# TiltyOmni.net
KiCad netlist of a schematic drawn in EAGLE
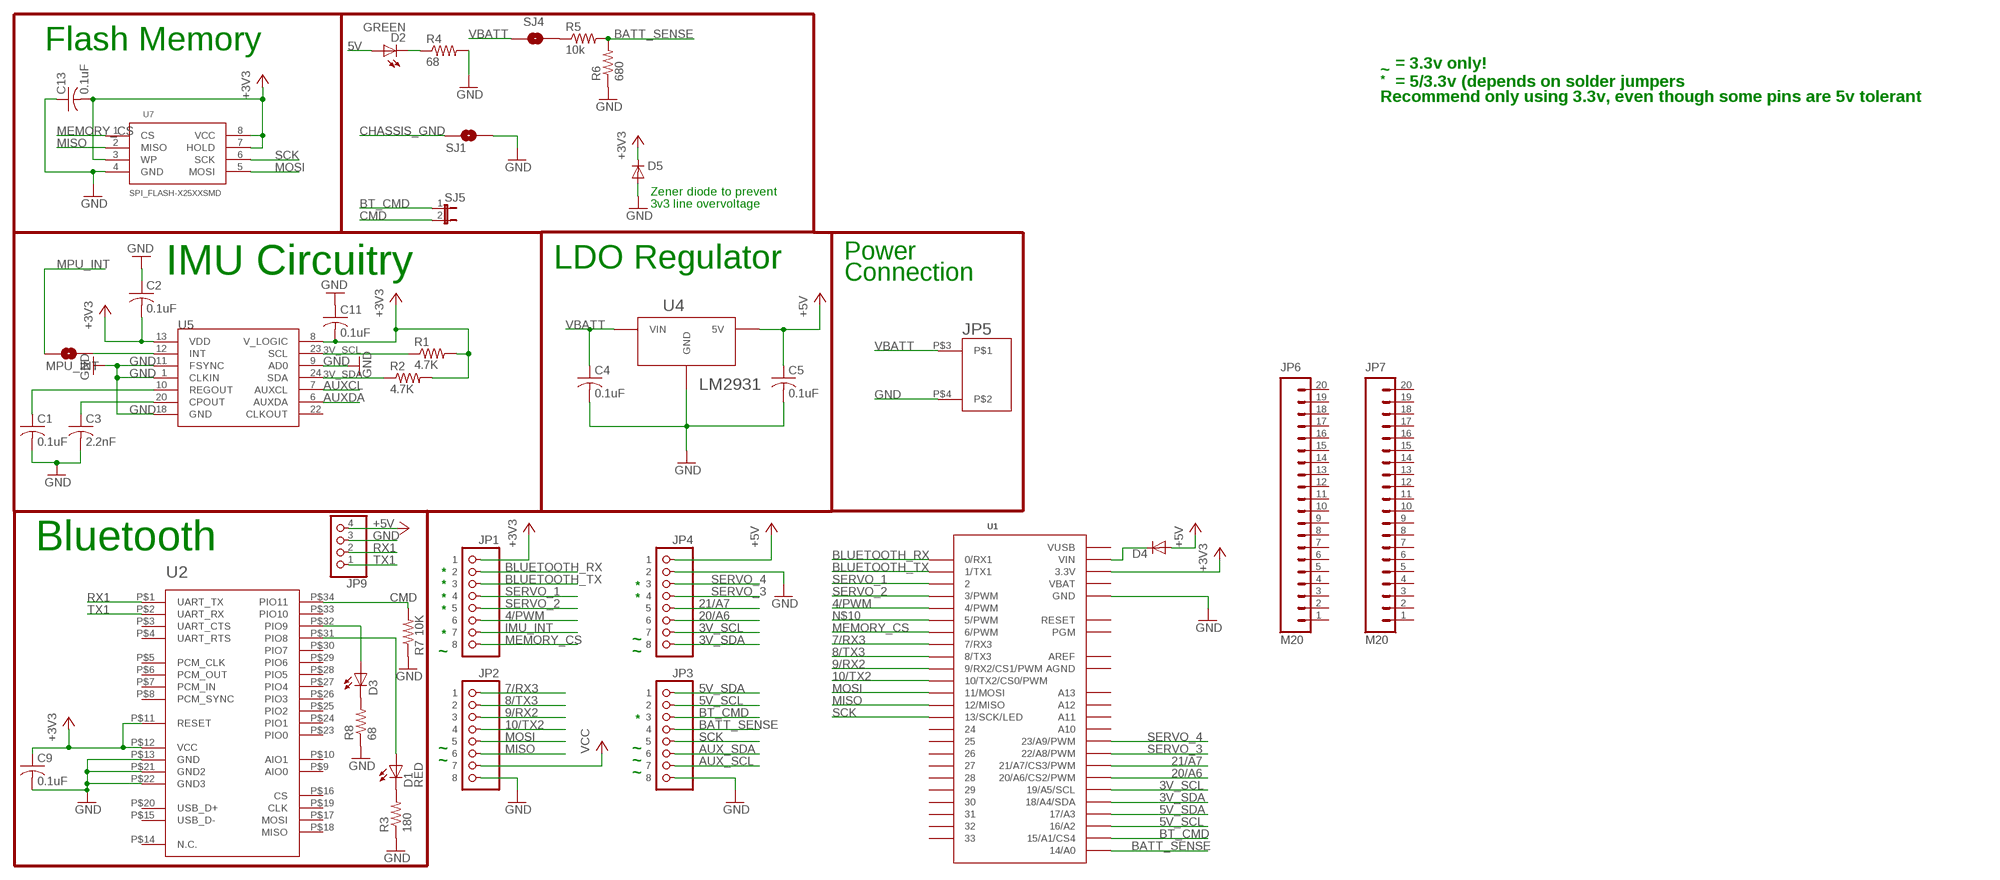
[diagram p0: schematic, sheet 1]

(export (version "E")
  (design (tool "Eeschema 10.0.6"))
  (components
    (comp (ref "C1")
      (value "0.1uF")
      (footprint "eagle-import:C0603")
      (libsource (lib "eagle-import") (part "C-USC0603"))
    )
    (comp (ref "C2")
      (value "0.1uF")
      (footprint "eagle-import:C0603")
      (libsource (lib "eagle-import") (part "C-USC0603"))
    )
    (comp (ref "C3")
      (value "2.2nF")
      (footprint "eagle-import:C0603")
      (libsource (lib "eagle-import") (part "C-USC0603"))
    )
    (comp (ref "C4")
      (value "0.1uF")
      (footprint "eagle-import:C0603")
      (libsource (lib "eagle-import") (part "C-USC0603"))
    )
    (comp (ref "C5")
      (value "0.1uF")
      (footprint "eagle-import:C0603")
      (libsource (lib "eagle-import") (part "C-USC0603"))
    )
    (comp (ref "C9")
      (value "0.1uF")
      (footprint "eagle-import:C0603")
      (libsource (lib "eagle-import") (part "C-USC0603"))
    )
    (comp (ref "C11")
      (value "0.1uF")
      (footprint "eagle-import:C0603")
      (libsource (lib "eagle-import") (part "C-USC0603"))
    )
    (comp (ref "C13")
      (value "0.1uF")
      (footprint "eagle-import:C0603")
      (libsource (lib "eagle-import") (part "C-USC0603"))
    )
    (comp (ref "D1")
      (value "RED")
      (footprint "eagle-import:LED-0805")
      (libsource (lib "eagle-import") (part "LED-GREENLED-0805_NO_SILK"))
    )
    (comp (ref "D2")
      (value "GREEN")
      (footprint "eagle-import:LED-0805")
      (libsource (lib "eagle-import") (part "LED-GREENLED-0805_NO_SILK"))
    )
    (comp (ref "D3")
      (value "YELLOW")
      (footprint "eagle-import:LED-0805")
      (libsource (lib "eagle-import") (part "LED-GREENLED-0805_NO_SILK"))
    )
    (comp (ref "D4")
      (value "DIODESOT23")
      (footprint "eagle-import:SOT23-3")
      (libsource (lib "eagle-import") (part "DIODESOT23"))
    )
    (comp (ref "D5")
      (value "DIODESOT23")
      (footprint "eagle-import:SOT23-3")
      (fields (field (name "PART#") "BZX84C3V3LT1GOSCT-ND"))
      (libsource (lib "eagle-import") (part "DIODESOT23"))
    )
    (comp (ref "JP1")
      (value "8-PIN_HEADER")
      (footprint "eagle-import:8-PIN_RECEPTACLE_LOCK_NO-SS")
      (libsource (lib "eagle-import") (part "8-PIN_HEADER"))
    )
    (comp (ref "JP2")
      (value "8-PIN_HEADER")
      (footprint "eagle-import:8-PIN_RECEPTACLE_LOCK_NO-SS")
      (libsource (lib "eagle-import") (part "8-PIN_HEADER"))
    )
    (comp (ref "JP3")
      (value "8-PIN_HEADER")
      (footprint "eagle-import:8-PIN_RECEPTACLE_LOCK_NO-SS")
      (libsource (lib "eagle-import") (part "8-PIN_HEADER"))
    )
    (comp (ref "JP4")
      (value "8-PIN_HEADER")
      (footprint "eagle-import:8-PIN_RECEPTACLE_LOCK_NO-SS")
      (libsource (lib "eagle-import") (part "8-PIN_HEADER"))
    )
    (comp (ref "JP5")
      (value "2-POS_SMD_TERM_BLOCK")
      (footprint "eagle-import:2-POS_SMD_TERMINAL_BLOCK")
      (fields (field (name "PART#") "277-2337-1-ND"))
      (libsource (lib "eagle-import") (part "2-POS_SMD_TERM_BLOCK"))
    )
    (comp (ref "JP6")
      (value "M20")
      (footprint "eagle-import:1X20")
      (libsource (lib "eagle-import") (part "M20"))
    )
    (comp (ref "JP7")
      (value "M20")
      (footprint "eagle-import:1X20")
      (libsource (lib "eagle-import") (part "M20"))
    )
    (comp (ref "JP9")
      (value "PINHD-1X41X04_NO_SS_LOCKING")
      (footprint "eagle-import:1X04_NO_SS_LOCKING")
      (libsource (lib "eagle-import") (part "PINHD-1X41X04_NO_SS_LOCKING"))
    )
    (comp (ref "MPU_INT")
      (value "SOLDERJUMPERNO")
      (footprint "eagle-import:SJ_2S-NO")
      (libsource (lib "eagle-import") (part "SOLDERJUMPERNO"))
    )
    (comp (ref "R1")
      (value "4.7K")
      (footprint "eagle-import:R0603")
      (libsource (lib "eagle-import") (part "R-US_R0603"))
    )
    (comp (ref "R2")
      (value "4.7K")
      (footprint "eagle-import:R0603")
      (libsource (lib "eagle-import") (part "R-US_R0603"))
    )
    (comp (ref "R3")
      (value "180")
      (footprint "eagle-import:R0603")
      (libsource (lib "eagle-import") (part "R-US_R0603"))
    )
    (comp (ref "R4")
      (value "68")
      (footprint "eagle-import:R0603")
      (libsource (lib "eagle-import") (part "R-US_R0603"))
    )
    (comp (ref "R5")
      (value "10k")
      (footprint "eagle-import:R0603")
      (libsource (lib "eagle-import") (part "R-US_R0603"))
    )
    (comp (ref "R6")
      (value "680")
      (footprint "eagle-import:R0603")
      (libsource (lib "eagle-import") (part "R-US_R0603"))
    )
    (comp (ref "R7")
      (value "10K")
      (footprint "eagle-import:R0603")
      (libsource (lib "eagle-import") (part "R-US_R0603"))
    )
    (comp (ref "R8")
      (value "68")
      (footprint "eagle-import:R0603")
      (libsource (lib "eagle-import") (part "R-US_R0603"))
    )
    (comp (ref "SJ1")
      (value "SOLDERJUMPERNO")
      (footprint "eagle-import:SJ_2S-NO")
      (libsource (lib "eagle-import") (part "SOLDERJUMPERNO"))
    )
    (comp (ref "SJ4")
      (value "SOLDERJUMPERTRACE")
      (footprint "eagle-import:SJ_2S-TRACE")
      (libsource (lib "eagle-import") (part "SOLDERJUMPERTRACE"))
    )
    (comp (ref "SJ5")
      (value "JUMPER-2SMD-NC")
      (footprint "eagle-import:SJ_2S")
      (libsource (lib "eagle-import") (part "JUMPER-2SMD-NC"))
    )
    (comp (ref "U1")
      (value "TEENSY_3.0_ALLPINS")
      (footprint "eagle-import:TEENSY_3.0_ALLPINS")
      (libsource (lib "eagle-import") (part "TEENSY_3.0_ALLPINS"))
    )
    (comp (ref "U2")
      (value "HC-09_BREAKOUT")
      (footprint "eagle-import:HC-09_BREAKOUT")
      (libsource (lib "eagle-import") (part "HC-09_BREAKOUT"))
    )
    (comp (ref "U4")
      (value "LM2931")
      (footprint "eagle-import:TO263")
      (libsource (lib "eagle-import") (part "LM2931"))
    )
    (comp (ref "U5")
      (value "MPU-6050")
      (footprint "eagle-import:QFN-24")
      (libsource (lib "eagle-import") (part "MPU-6050"))
    )
    (comp (ref "U7")
      (value "SPI_FLASH-X25XXSMD")
      (footprint "eagle-import:SO08")
      (fields (field (name "PART#") "S25FL204K0TMFI043"))
      (libsource (lib "eagle-import") (part "SPI_FLASH-X25XXSMD"))
    )
  )
  (nets
    (net (code "1") (name "+3V3") (class "Default")
      (node (ref "C11") (pin "2") (pinfunction "2_2") (pintype "passive"))
      (node (ref "C13") (pin "2") (pinfunction "2_2") (pintype "passive"))
      (node (ref "C2") (pin "2") (pinfunction "2_2") (pintype "passive"))
      (node (ref "C9") (pin "1") (pinfunction "1_1") (pintype "passive"))
      (node (ref "D5") (pin "3") (pinfunction "C_3") (pintype "passive"))
      (node (ref "JP1") (pin "P$1") (pinfunction "1_P$1") (pintype "passive"))
      (node (ref "R1") (pin "2") (pinfunction "2_2") (pintype "passive"))
      (node (ref "R2") (pin "2") (pinfunction "2_2") (pintype "passive"))
      (node (ref "U1") (pin "3.3V") (pinfunction "3.3V_3.3V") (pintype "power_in"))
      (node (ref "U1") (pin "3.3V1") (pinfunction "3.3V_3.3V1") (pintype "power_in"))
      (node (ref "U1") (pin "3.3V2") (pinfunction "3.3V_3.3V2") (pintype "power_in"))
      (node (ref "U2") (pin "P$11") (pinfunction "RESET_P$11") (pintype "bidirectional"))
      (node (ref "U2") (pin "P$12") (pinfunction "VCC_P$12") (pintype "bidirectional"))
      (node (ref "U5") (pin "13") (pinfunction "VDD_13") (pintype "bidirectional"))
      (node (ref "U5") (pin "8") (pinfunction "V_LOGIC_8") (pintype "bidirectional"))
      (node (ref "U7") (pin "3") (pinfunction "WP_3") (pintype "bidirectional"))
      (node (ref "U7") (pin "7") (pinfunction "HOLD_7") (pintype "bidirectional"))
      (node (ref "U7") (pin "8") (pinfunction "VCC_8") (pintype "bidirectional"))
    )
    (net (code "2") (name "+5V") (class "Default")
      (node (ref "C5") (pin "1") (pinfunction "1_1") (pintype "passive"))
      (node (ref "D4") (pin "1") (pinfunction "A_1") (pintype "passive"))
      (node (ref "JP4") (pin "P$1") (pinfunction "1_P$1") (pintype "passive"))
      (node (ref "JP9") (pin "4") (pinfunction "4_4") (pintype "passive"))
      (node (ref "U4") (pin "P$3") (pinfunction "5V_P$3") (pintype "bidirectional"))
    )
    (net (code "3") (name "/3V_SCL") (class "Default")
      (node (ref "JP4") (pin "P$7") (pinfunction "7_P$7") (pintype "passive"))
      (node (ref "R1") (pin "1") (pinfunction "1_1") (pintype "passive"))
      (node (ref "U1") (pin "19/A5") (pinfunction "19/A5/SCL_19/A5") (pintype "bidirectional"))
      (node (ref "U5") (pin "23") (pinfunction "SCL_23") (pintype "bidirectional"))
    )
    (net (code "4") (name "/3V_SDA") (class "Default")
      (node (ref "JP4") (pin "P$8") (pinfunction "8_P$8") (pintype "passive"))
      (node (ref "R2") (pin "1") (pinfunction "1_1") (pintype "passive"))
      (node (ref "U1") (pin "18/A4") (pinfunction "18/A4/SDA_18/A4") (pintype "bidirectional"))
      (node (ref "U5") (pin "24") (pinfunction "SDA_24") (pintype "bidirectional"))
    )
    (net (code "5") (name "/4{slash}PWM") (class "Default")
      (node (ref "JP1") (pin "P$6") (pinfunction "6_P$6") (pintype "passive"))
      (node (ref "U1") (pin "4") (pinfunction "4/PWM_4") (pintype "bidirectional"))
    )
    (net (code "6") (name "/5V") (class "Default")
      (node (ref "D2") (pin "1") (pinfunction "A_1") (pintype "passive"))
    )
    (net (code "7") (name "/5V_SCL") (class "Default")
      (node (ref "JP3") (pin "P$2") (pinfunction "2_P$2") (pintype "passive"))
      (node (ref "U1") (pin "16/A2") (pinfunction "16/A2_16/A2") (pintype "bidirectional"))
    )
    (net (code "8") (name "/5V_SDA") (class "Default")
      (node (ref "JP3") (pin "P$1") (pinfunction "1_P$1") (pintype "passive"))
      (node (ref "U1") (pin "17/A3") (pinfunction "17/A3_17/A3") (pintype "bidirectional"))
    )
    (net (code "9") (name "/7{slash}RX3") (class "Default")
      (node (ref "JP2") (pin "P$1") (pinfunction "1_P$1") (pintype "passive"))
      (node (ref "U1") (pin "7") (pinfunction "7/RX3_7") (pintype "bidirectional"))
    )
    (net (code "10") (name "/8{slash}TX3") (class "Default")
      (node (ref "JP2") (pin "P$2") (pinfunction "2_P$2") (pintype "passive"))
      (node (ref "U1") (pin "8") (pinfunction "8/TX3_8") (pintype "bidirectional"))
    )
    (net (code "11") (name "/9{slash}RX2") (class "Default")
      (node (ref "JP2") (pin "P$3") (pinfunction "3_P$3") (pintype "passive"))
      (node (ref "U1") (pin "9") (pinfunction "9/RX2/CS1/PWM_9") (pintype "bidirectional"))
    )
    (net (code "12") (name "/10{slash}TX2") (class "Default")
      (node (ref "JP2") (pin "P$4") (pinfunction "4_P$4") (pintype "passive"))
      (node (ref "U1") (pin "10") (pinfunction "10/TX2/CS0/PWM_10") (pintype "bidirectional"))
    )
    (net (code "13") (name "/20{slash}A6") (class "Default")
      (node (ref "JP4") (pin "P$6") (pinfunction "6_P$6") (pintype "passive"))
      (node (ref "U1") (pin "20/A6") (pinfunction "20/A6/CS2/PWM_20/A6") (pintype "bidirectional"))
    )
    (net (code "14") (name "/21{slash}A7") (class "Default")
      (node (ref "JP4") (pin "P$5") (pinfunction "5_P$5") (pintype "passive"))
      (node (ref "U1") (pin "21/A7") (pinfunction "21/A7/CS3/PWM_21/A7") (pintype "bidirectional"))
    )
    (net (code "15") (name "/AGND") (class "Default")
      (node (ref "U1") (pin "AGND") (pinfunction "AGND_AGND") (pintype "power_in"))
    )
    (net (code "16") (name "/AREF") (class "Default")
      (node (ref "U1") (pin "AREF") (pinfunction "AREF_AREF") (pintype "power_in"))
    )
    (net (code "17") (name "/AUXCL") (class "Default")
      (node (ref "U5") (pin "7") (pinfunction "AUXCL_7") (pintype "bidirectional"))
    )
    (net (code "18") (name "/AUXDA") (class "Default")
      (node (ref "U5") (pin "6") (pinfunction "AUXDA_6") (pintype "bidirectional"))
    )
    (net (code "19") (name "/AUX_SCL") (class "Default")
      (node (ref "JP3") (pin "P$7") (pinfunction "7_P$7") (pintype "passive"))
    )
    (net (code "20") (name "/AUX_SDA") (class "Default")
      (node (ref "JP3") (pin "P$6") (pinfunction "6_P$6") (pintype "passive"))
    )
    (net (code "21") (name "/BATT_SENSE") (class "Default")
      (node (ref "JP3") (pin "P$4") (pinfunction "4_P$4") (pintype "passive"))
      (node (ref "R5") (pin "2") (pinfunction "2_2") (pintype "passive"))
      (node (ref "R6") (pin "2") (pinfunction "2_2") (pintype "passive"))
      (node (ref "U1") (pin "14/A0") (pinfunction "14/A0_14/A0") (pintype "bidirectional"))
    )
    (net (code "22") (name "/BLUETOOTH_RX") (class "Default")
      (node (ref "JP1") (pin "P$2") (pinfunction "2_P$2") (pintype "passive"))
      (node (ref "U1") (pin "0") (pinfunction "0/RX1_0") (pintype "bidirectional"))
    )
    (net (code "23") (name "/BLUETOOTH_TX") (class "Default")
      (node (ref "JP1") (pin "P$3") (pinfunction "3_P$3") (pintype "passive"))
      (node (ref "U1") (pin "1") (pinfunction "1/TX1_1") (pintype "bidirectional"))
    )
    (net (code "24") (name "/BT_CMD") (class "Default")
      (node (ref "JP3") (pin "P$3") (pinfunction "3_P$3") (pintype "passive"))
      (node (ref "SJ5") (pin "1") (pinfunction "1_1") (pintype "passive"))
      (node (ref "U1") (pin "15/A1") (pinfunction "15/A1/CS4_15/A1") (pintype "bidirectional"))
    )
    (net (code "25") (name "/CHASSIS_GND") (class "Default")
      (node (ref "SJ1") (pin "1") (pinfunction "1_1") (pintype "passive"))
    )
    (net (code "26") (name "/CMD") (class "Default")
      (node (ref "R7") (pin "2") (pinfunction "2_2") (pintype "passive"))
      (node (ref "SJ5") (pin "2") (pinfunction "2_2") (pintype "passive"))
      (node (ref "U2") (pin "P$34") (pinfunction "PIO11_P$34") (pintype "bidirectional"))
    )
    (net (code "27") (name "/IMU_INT") (class "Default")
      (node (ref "JP1") (pin "P$7") (pinfunction "7_P$7") (pintype "passive"))
    )
    (net (code "28") (name "/MEMORY_CS") (class "Default")
      (node (ref "JP1") (pin "P$8") (pinfunction "8_P$8") (pintype "passive"))
      (node (ref "U1") (pin "6") (pinfunction "6/PWM_6") (pintype "bidirectional"))
      (node (ref "U7") (pin "1") (pinfunction "CS_1") (pintype "bidirectional"))
    )
    (net (code "29") (name "/MISO") (class "Default")
      (node (ref "JP2") (pin "P$6") (pinfunction "6_P$6") (pintype "passive"))
      (node (ref "U1") (pin "12") (pinfunction "12/MISO_12") (pintype "bidirectional"))
      (node (ref "U7") (pin "2") (pinfunction "MISO_2") (pintype "bidirectional"))
    )
    (net (code "30") (name "/MOSI") (class "Default")
      (node (ref "JP2") (pin "P$5") (pinfunction "5_P$5") (pintype "passive"))
      (node (ref "U1") (pin "11") (pinfunction "11/MOSI_11") (pintype "bidirectional"))
      (node (ref "U7") (pin "5") (pinfunction "MOSI_5") (pintype "bidirectional"))
    )
    (net (code "31") (name "/MPU_INT") (class "Default")
      (node (ref "MPU_INT") (pin "1") (pinfunction "1_1") (pintype "passive"))
    )
    (net (code "32") (name "/N$10") (class "Default")
      (node (ref "U1") (pin "5") (pinfunction "5/PWM_5") (pintype "bidirectional"))
    )
    (net (code "33") (name "/RX1") (class "Default")
      (node (ref "JP9") (pin "2") (pinfunction "2_2") (pintype "passive"))
      (node (ref "U2") (pin "P$1") (pinfunction "UART_TX_P$1") (pintype "bidirectional"))
    )
    (net (code "34") (name "/SCK") (class "Default")
      (node (ref "JP3") (pin "P$5") (pinfunction "5_P$5") (pintype "passive"))
      (node (ref "U1") (pin "13") (pinfunction "13/SCK/LED_13") (pintype "bidirectional"))
      (node (ref "U7") (pin "6") (pinfunction "SCK_6") (pintype "bidirectional"))
    )
    (net (code "35") (name "/SERVO_1") (class "Default")
      (node (ref "JP1") (pin "P$4") (pinfunction "4_P$4") (pintype "passive"))
      (node (ref "U1") (pin "2") (pinfunction "2_2") (pintype "bidirectional"))
    )
    (net (code "36") (name "/SERVO_2") (class "Default")
      (node (ref "JP1") (pin "P$5") (pinfunction "5_P$5") (pintype "passive"))
      (node (ref "U1") (pin "3") (pinfunction "3/PWM_3") (pintype "bidirectional"))
    )
    (net (code "37") (name "/SERVO_3") (class "Default")
      (node (ref "JP4") (pin "P$4") (pinfunction "4_P$4") (pintype "passive"))
      (node (ref "U1") (pin "22/A8") (pinfunction "22/A8/PWM_22/A8") (pintype "bidirectional"))
    )
    (net (code "38") (name "/SERVO_4") (class "Default")
      (node (ref "JP4") (pin "P$3") (pinfunction "3_P$3") (pintype "passive"))
      (node (ref "U1") (pin "23/A9") (pinfunction "23/A9/PWM_23/A9") (pintype "bidirectional"))
    )
    (net (code "39") (name "/TX1") (class "Default")
      (node (ref "JP9") (pin "1") (pinfunction "1_1") (pintype "passive"))
      (node (ref "U2") (pin "P$2") (pinfunction "UART_RX_P$2") (pintype "bidirectional"))
    )
    (net (code "40") (name "/VBAT") (class "Default")
      (node (ref "U1") (pin "VBAT") (pinfunction "VBAT_VBAT") (pintype "power_in"))
    )
    (net (code "41") (name "/VBATT") (class "Default")
      (node (ref "C4") (pin "1") (pinfunction "1_1") (pintype "passive"))
      (node (ref "JP5") (pin "P$3") (pinfunction "P$1_P$3") (pintype "bidirectional"))
      (node (ref "SJ4") (pin "1") (pinfunction "1_1") (pintype "passive"))
      (node (ref "U4") (pin "P$2") (pinfunction "VIN_P$2") (pintype "bidirectional"))
    )
    (net (code "42") (name "/VUSB") (class "Default")
      (node (ref "U1") (pin "VUSB") (pinfunction "VUSB_VUSB") (pintype "power_in"))
    )
    (net (code "43") (name "GND") (class "Default")
      (node (ref "C1") (pin "2") (pinfunction "2_2") (pintype "passive"))
      (node (ref "C11") (pin "1") (pinfunction "1_1") (pintype "passive"))
      (node (ref "C13") (pin "1") (pinfunction "1_1") (pintype "passive"))
      (node (ref "C2") (pin "1") (pinfunction "1_1") (pintype "passive"))
      (node (ref "C3") (pin "2") (pinfunction "2_2") (pintype "passive"))
      (node (ref "C4") (pin "2") (pinfunction "2_2") (pintype "passive"))
      (node (ref "C5") (pin "2") (pinfunction "2_2") (pintype "passive"))
      (node (ref "C9") (pin "2") (pinfunction "2_2") (pintype "passive"))
      (node (ref "D5") (pin "1") (pinfunction "A_1") (pintype "passive"))
      (node (ref "JP2") (pin "P$8") (pinfunction "8_P$8") (pintype "passive"))
      (node (ref "JP3") (pin "P$8") (pinfunction "8_P$8") (pintype "passive"))
      (node (ref "JP4") (pin "P$2") (pinfunction "2_P$2") (pintype "passive"))
      (node (ref "JP5") (pin "P$4") (pinfunction "P$2_P$4") (pintype "bidirectional"))
      (node (ref "JP9") (pin "3") (pinfunction "3_3") (pintype "passive"))
      (node (ref "R3") (pin "1") (pinfunction "1_1") (pintype "passive"))
      (node (ref "R4") (pin "2") (pinfunction "2_2") (pintype "passive"))
      (node (ref "R6") (pin "1") (pinfunction "1_1") (pintype "passive"))
      (node (ref "R7") (pin "1") (pinfunction "1_1") (pintype "passive"))
      (node (ref "R8") (pin "1") (pinfunction "1_1") (pintype "passive"))
      (node (ref "SJ1") (pin "2") (pinfunction "2_2") (pintype "passive"))
      (node (ref "U1") (pin "GND") (pinfunction "GND_GND") (pintype "power_in"))
      (node (ref "U1") (pin "GND1") (pinfunction "GND_GND1") (pintype "power_in"))
      (node (ref "U1") (pin "GND2") (pinfunction "GND_GND2") (pintype "power_in"))
      (node (ref "U2") (pin "P$13") (pinfunction "GND_P$13") (pintype "bidirectional"))
      (node (ref "U2") (pin "P$21") (pinfunction "GND2_P$21") (pintype "bidirectional"))
      (node (ref "U2") (pin "P$22") (pinfunction "GND3_P$22") (pintype "bidirectional"))
      (node (ref "U4") (pin "P$1") (pinfunction "GND_P$1") (pintype "bidirectional"))
      (node (ref "U5") (pin "1") (pinfunction "CLKIN_1") (pintype "bidirectional"))
      (node (ref "U5") (pin "11") (pinfunction "FSYNC_11") (pintype "bidirectional"))
      (node (ref "U5") (pin "18") (pinfunction "GND_18") (pintype "bidirectional"))
      (node (ref "U5") (pin "9") (pinfunction "AD0_9") (pintype "bidirectional"))
      (node (ref "U7") (pin "4") (pinfunction "GND_4") (pintype "bidirectional"))
    )
    (net (code "44") (name "Net-(D1-A)") (class "Default")
      (node (ref "D1") (pin "1") (pinfunction "A_1") (pintype "passive"))
      (node (ref "U2") (pin "P$31") (pinfunction "PIO8_P$31") (pintype "bidirectional"))
    )
    (net (code "45") (name "Net-(D1-C)") (class "Default")
      (node (ref "D1") (pin "2") (pinfunction "C_2") (pintype "passive"))
      (node (ref "R3") (pin "2") (pinfunction "2_2") (pintype "passive"))
    )
    (net (code "46") (name "Net-(D2-C)") (class "Default")
      (node (ref "D2") (pin "2") (pinfunction "C_2") (pintype "passive"))
      (node (ref "R4") (pin "1") (pinfunction "1_1") (pintype "passive"))
    )
    (net (code "47") (name "Net-(D3-A)") (class "Default")
      (node (ref "D3") (pin "1") (pinfunction "A_1") (pintype "passive"))
      (node (ref "U2") (pin "P$32") (pinfunction "PIO9_P$32") (pintype "bidirectional"))
    )
    (net (code "48") (name "Net-(D3-C)") (class "Default")
      (node (ref "D3") (pin "2") (pinfunction "C_2") (pintype "passive"))
      (node (ref "R8") (pin "2") (pinfunction "2_2") (pintype "passive"))
    )
    (net (code "49") (name "Net-(D4-C)") (class "Default")
      (node (ref "D4") (pin "3") (pinfunction "C_3") (pintype "passive"))
      (node (ref "U1") (pin "VIN") (pinfunction "VIN_VIN") (pintype "power_in"))
    )
    (net (code "50") (name "Net-(R5-Pad1)") (class "Default")
      (node (ref "R5") (pin "1") (pinfunction "1_1") (pintype "passive"))
      (node (ref "SJ4") (pin "2") (pinfunction "2_2") (pintype "passive"))
    )
    (net (code "51") (name "Net-(U5-CPOUT)") (class "Default")
      (node (ref "C3") (pin "1") (pinfunction "1_1") (pintype "passive"))
      (node (ref "U5") (pin "20") (pinfunction "CPOUT_20") (pintype "bidirectional"))
    )
    (net (code "52") (name "Net-(U5-INT)") (class "Default")
      (node (ref "MPU_INT") (pin "2") (pinfunction "2_2") (pintype "passive"))
      (node (ref "U5") (pin "12") (pinfunction "INT_12") (pintype "bidirectional"))
    )
    (net (code "53") (name "Net-(U5-REGOUT)") (class "Default")
      (node (ref "C1") (pin "1") (pinfunction "1_1") (pintype "passive"))
      (node (ref "U5") (pin "10") (pinfunction "REGOUT_10") (pintype "bidirectional"))
    )
    (net (code "54") (name "VCC") (class "Default")
      (node (ref "JP2") (pin "P$7") (pinfunction "7_P$7") (pintype "passive"))
    )
    (net (code "55") (name "unconnected-(JP6-Pad1)") (class "Default")
      (node (ref "JP6") (pin "1") (pinfunction "1_1") (pintype "passive"))
    )
    (net (code "56") (name "unconnected-(JP6-Pad2)") (class "Default")
      (node (ref "JP6") (pin "2") (pinfunction "2_2") (pintype "passive"))
    )
    (net (code "57") (name "unconnected-(JP6-Pad3)") (class "Default")
      (node (ref "JP6") (pin "3") (pinfunction "3_3") (pintype "passive"))
    )
    (net (code "58") (name "unconnected-(JP6-Pad4)") (class "Default")
      (node (ref "JP6") (pin "4") (pinfunction "4_4") (pintype "passive"))
    )
    (net (code "59") (name "unconnected-(JP6-Pad5)") (class "Default")
      (node (ref "JP6") (pin "5") (pinfunction "5_5") (pintype "passive"))
    )
    (net (code "60") (name "unconnected-(JP6-Pad6)") (class "Default")
      (node (ref "JP6") (pin "6") (pinfunction "6_6") (pintype "passive"))
    )
    (net (code "61") (name "unconnected-(JP6-Pad7)") (class "Default")
      (node (ref "JP6") (pin "7") (pinfunction "7_7") (pintype "passive"))
    )
    (net (code "62") (name "unconnected-(JP6-Pad8)") (class "Default")
      (node (ref "JP6") (pin "8") (pinfunction "8_8") (pintype "passive"))
    )
    (net (code "63") (name "unconnected-(JP6-Pad9)") (class "Default")
      (node (ref "JP6") (pin "9") (pinfunction "9_9") (pintype "passive"))
    )
    (net (code "64") (name "unconnected-(JP6-Pad10)") (class "Default")
      (node (ref "JP6") (pin "10") (pinfunction "10_10") (pintype "passive"))
    )
    (net (code "65") (name "unconnected-(JP6-Pad11)") (class "Default")
      (node (ref "JP6") (pin "11") (pinfunction "11_11") (pintype "passive"))
    )
    (net (code "66") (name "unconnected-(JP6-Pad12)") (class "Default")
      (node (ref "JP6") (pin "12") (pinfunction "12_12") (pintype "passive"))
    )
    (net (code "67") (name "unconnected-(JP6-Pad13)") (class "Default")
      (node (ref "JP6") (pin "13") (pinfunction "13_13") (pintype "passive"))
    )
    (net (code "68") (name "unconnected-(JP6-Pad14)") (class "Default")
      (node (ref "JP6") (pin "14") (pinfunction "14_14") (pintype "passive"))
    )
    (net (code "69") (name "unconnected-(JP6-Pad15)") (class "Default")
      (node (ref "JP6") (pin "15") (pinfunction "15_15") (pintype "passive"))
    )
    (net (code "70") (name "unconnected-(JP6-Pad16)") (class "Default")
      (node (ref "JP6") (pin "16") (pinfunction "16_16") (pintype "passive"))
    )
    (net (code "71") (name "unconnected-(JP6-Pad17)") (class "Default")
      (node (ref "JP6") (pin "17") (pinfunction "17_17") (pintype "passive"))
    )
    (net (code "72") (name "unconnected-(JP6-Pad18)") (class "Default")
      (node (ref "JP6") (pin "18") (pinfunction "18_18") (pintype "passive"))
    )
    (net (code "73") (name "unconnected-(JP6-Pad19)") (class "Default")
      (node (ref "JP6") (pin "19") (pinfunction "19_19") (pintype "passive"))
    )
    (net (code "74") (name "unconnected-(JP6-Pad20)") (class "Default")
      (node (ref "JP6") (pin "20") (pinfunction "20_20") (pintype "passive"))
    )
    (net (code "75") (name "unconnected-(JP7-Pad1)") (class "Default")
      (node (ref "JP7") (pin "1") (pinfunction "1_1") (pintype "passive"))
    )
    (net (code "76") (name "unconnected-(JP7-Pad2)") (class "Default")
      (node (ref "JP7") (pin "2") (pinfunction "2_2") (pintype "passive"))
    )
    (net (code "77") (name "unconnected-(JP7-Pad3)") (class "Default")
      (node (ref "JP7") (pin "3") (pinfunction "3_3") (pintype "passive"))
    )
    (net (code "78") (name "unconnected-(JP7-Pad4)") (class "Default")
      (node (ref "JP7") (pin "4") (pinfunction "4_4") (pintype "passive"))
    )
    (net (code "79") (name "unconnected-(JP7-Pad5)") (class "Default")
      (node (ref "JP7") (pin "5") (pinfunction "5_5") (pintype "passive"))
    )
    (net (code "80") (name "unconnected-(JP7-Pad6)") (class "Default")
      (node (ref "JP7") (pin "6") (pinfunction "6_6") (pintype "passive"))
    )
    (net (code "81") (name "unconnected-(JP7-Pad7)") (class "Default")
      (node (ref "JP7") (pin "7") (pinfunction "7_7") (pintype "passive"))
    )
    (net (code "82") (name "unconnected-(JP7-Pad8)") (class "Default")
      (node (ref "JP7") (pin "8") (pinfunction "8_8") (pintype "passive"))
    )
    (net (code "83") (name "unconnected-(JP7-Pad9)") (class "Default")
      (node (ref "JP7") (pin "9") (pinfunction "9_9") (pintype "passive"))
    )
    (net (code "84") (name "unconnected-(JP7-Pad10)") (class "Default")
      (node (ref "JP7") (pin "10") (pinfunction "10_10") (pintype "passive"))
    )
    (net (code "85") (name "unconnected-(JP7-Pad11)") (class "Default")
      (node (ref "JP7") (pin "11") (pinfunction "11_11") (pintype "passive"))
    )
    (net (code "86") (name "unconnected-(JP7-Pad12)") (class "Default")
      (node (ref "JP7") (pin "12") (pinfunction "12_12") (pintype "passive"))
    )
    (net (code "87") (name "unconnected-(JP7-Pad13)") (class "Default")
      (node (ref "JP7") (pin "13") (pinfunction "13_13") (pintype "passive"))
    )
    (net (code "88") (name "unconnected-(JP7-Pad14)") (class "Default")
      (node (ref "JP7") (pin "14") (pinfunction "14_14") (pintype "passive"))
    )
    (net (code "89") (name "unconnected-(JP7-Pad15)") (class "Default")
      (node (ref "JP7") (pin "15") (pinfunction "15_15") (pintype "passive"))
    )
    (net (code "90") (name "unconnected-(JP7-Pad16)") (class "Default")
      (node (ref "JP7") (pin "16") (pinfunction "16_16") (pintype "passive"))
    )
    (net (code "91") (name "unconnected-(JP7-Pad17)") (class "Default")
      (node (ref "JP7") (pin "17") (pinfunction "17_17") (pintype "passive"))
    )
    (net (code "92") (name "unconnected-(JP7-Pad18)") (class "Default")
      (node (ref "JP7") (pin "18") (pinfunction "18_18") (pintype "passive"))
    )
    (net (code "93") (name "unconnected-(JP7-Pad19)") (class "Default")
      (node (ref "JP7") (pin "19") (pinfunction "19_19") (pintype "passive"))
    )
    (net (code "94") (name "unconnected-(JP7-Pad20)") (class "Default")
      (node (ref "JP7") (pin "20") (pinfunction "20_20") (pintype "passive"))
    )
    (net (code "95") (name "unconnected-(U1-Pad24)") (class "Default")
      (node (ref "U1") (pin "24") (pinfunction "24_24") (pintype "bidirectional"))
    )
    (net (code "96") (name "unconnected-(U1-Pad25)") (class "Default")
      (node (ref "U1") (pin "25") (pinfunction "25_25") (pintype "bidirectional"))
    )
    (net (code "97") (name "unconnected-(U1-Pad26)") (class "Default")
      (node (ref "U1") (pin "26") (pinfunction "26_26") (pintype "bidirectional"))
    )
    (net (code "98") (name "unconnected-(U1-Pad27)") (class "Default")
      (node (ref "U1") (pin "27") (pinfunction "27_27") (pintype "bidirectional"))
    )
    (net (code "99") (name "unconnected-(U1-Pad28)") (class "Default")
      (node (ref "U1") (pin "28") (pinfunction "28_28") (pintype "bidirectional"))
    )
    (net (code "100") (name "unconnected-(U1-Pad29)") (class "Default")
      (node (ref "U1") (pin "29") (pinfunction "29_29") (pintype "bidirectional"))
    )
    (net (code "101") (name "unconnected-(U1-Pad30)") (class "Default")
      (node (ref "U1") (pin "30") (pinfunction "30_30") (pintype "bidirectional"))
    )
    (net (code "102") (name "unconnected-(U1-Pad31)") (class "Default")
      (node (ref "U1") (pin "31") (pinfunction "31_31") (pintype "bidirectional"))
    )
    (net (code "103") (name "unconnected-(U1-Pad32)") (class "Default")
      (node (ref "U1") (pin "32") (pinfunction "32_32") (pintype "bidirectional"))
    )
    (net (code "104") (name "unconnected-(U1-Pad33)") (class "Default")
      (node (ref "U1") (pin "33") (pinfunction "33_33") (pintype "bidirectional"))
    )
    (net (code "105") (name "unconnected-(U1-PadA10)") (class "Default")
      (node (ref "U1") (pin "A10") (pinfunction "A10_A10") (pintype "bidirectional"))
    )
    (net (code "106") (name "unconnected-(U1-PadA11)") (class "Default")
      (node (ref "U1") (pin "A11") (pinfunction "A11_A11") (pintype "bidirectional"))
    )
    (net (code "107") (name "unconnected-(U1-PadA12)") (class "Default")
      (node (ref "U1") (pin "A12") (pinfunction "A12_A12") (pintype "bidirectional"))
    )
    (net (code "108") (name "unconnected-(U1-PadA13)") (class "Default")
      (node (ref "U1") (pin "A13") (pinfunction "A13_A13") (pintype "bidirectional"))
    )
    (net (code "109") (name "unconnected-(U1-PadPGM)") (class "Default")
      (node (ref "U1") (pin "PGM") (pinfunction "PGM_PGM") (pintype "bidirectional"))
    )
    (net (code "110") (name "unconnected-(U1-PadRESET)") (class "Default")
      (node (ref "U1") (pin "RESET") (pinfunction "RESET_RESET") (pintype "bidirectional"))
    )
    (net (code "111") (name "unconnected-(U2-AIO0-PadP$9)") (class "Default")
      (node (ref "U2") (pin "P$9") (pinfunction "AIO0_P$9") (pintype "bidirectional"))
    )
    (net (code "112") (name "unconnected-(U2-AIO1-PadP$10)") (class "Default")
      (node (ref "U2") (pin "P$10") (pinfunction "AIO1_P$10") (pintype "bidirectional"))
    )
    (net (code "113") (name "unconnected-(U2-CLK-PadP$19)") (class "Default")
      (node (ref "U2") (pin "P$19") (pinfunction "CLK_P$19") (pintype "bidirectional"))
    )
    (net (code "114") (name "unconnected-(U2-CS-PadP$16)") (class "Default")
      (node (ref "U2") (pin "P$16") (pinfunction "CS_P$16") (pintype "bidirectional"))
    )
    (net (code "115") (name "unconnected-(U2-MISO-PadP$18)") (class "Default")
      (node (ref "U2") (pin "P$18") (pinfunction "MISO_P$18") (pintype "bidirectional"))
    )
    (net (code "116") (name "unconnected-(U2-MOSI-PadP$17)") (class "Default")
      (node (ref "U2") (pin "P$17") (pinfunction "MOSI_P$17") (pintype "bidirectional"))
    )
    (net (code "117") (name "unconnected-(U2-N.C.-PadP$14)") (class "Default")
      (node (ref "U2") (pin "P$14") (pinfunction "N.C._P$14") (pintype "bidirectional"))
    )
    (net (code "118") (name "unconnected-(U2-PCM_CLK-PadP$5)") (class "Default")
      (node (ref "U2") (pin "P$5") (pinfunction "PCM_CLK_P$5") (pintype "bidirectional"))
    )
    (net (code "119") (name "unconnected-(U2-PCM_IN-PadP$7)") (class "Default")
      (node (ref "U2") (pin "P$7") (pinfunction "PCM_IN_P$7") (pintype "bidirectional"))
    )
    (net (code "120") (name "unconnected-(U2-PCM_OUT-PadP$6)") (class "Default")
      (node (ref "U2") (pin "P$6") (pinfunction "PCM_OUT_P$6") (pintype "bidirectional"))
    )
    (net (code "121") (name "unconnected-(U2-PCM_SYNC-PadP$8)") (class "Default")
      (node (ref "U2") (pin "P$8") (pinfunction "PCM_SYNC_P$8") (pintype "bidirectional"))
    )
    (net (code "122") (name "unconnected-(U2-PIO0-PadP$23)") (class "Default")
      (node (ref "U2") (pin "P$23") (pinfunction "PIO0_P$23") (pintype "bidirectional"))
    )
    (net (code "123") (name "unconnected-(U2-PIO1-PadP$24)") (class "Default")
      (node (ref "U2") (pin "P$24") (pinfunction "PIO1_P$24") (pintype "bidirectional"))
    )
    (net (code "124") (name "unconnected-(U2-PIO2-PadP$25)") (class "Default")
      (node (ref "U2") (pin "P$25") (pinfunction "PIO2_P$25") (pintype "bidirectional"))
    )
    (net (code "125") (name "unconnected-(U2-PIO3-PadP$26)") (class "Default")
      (node (ref "U2") (pin "P$26") (pinfunction "PIO3_P$26") (pintype "bidirectional"))
    )
    (net (code "126") (name "unconnected-(U2-PIO4-PadP$27)") (class "Default")
      (node (ref "U2") (pin "P$27") (pinfunction "PIO4_P$27") (pintype "bidirectional"))
    )
    (net (code "127") (name "unconnected-(U2-PIO5-PadP$28)") (class "Default")
      (node (ref "U2") (pin "P$28") (pinfunction "PIO5_P$28") (pintype "bidirectional"))
    )
    (net (code "128") (name "unconnected-(U2-PIO6-PadP$29)") (class "Default")
      (node (ref "U2") (pin "P$29") (pinfunction "PIO6_P$29") (pintype "bidirectional"))
    )
    (net (code "129") (name "unconnected-(U2-PIO7-PadP$30)") (class "Default")
      (node (ref "U2") (pin "P$30") (pinfunction "PIO7_P$30") (pintype "bidirectional"))
    )
    (net (code "130") (name "unconnected-(U2-PIO10-PadP$33)") (class "Default")
      (node (ref "U2") (pin "P$33") (pinfunction "PIO10_P$33") (pintype "bidirectional"))
    )
    (net (code "131") (name "unconnected-(U2-UART_CTS-PadP$3)") (class "Default")
      (node (ref "U2") (pin "P$3") (pinfunction "UART_CTS_P$3") (pintype "bidirectional"))
    )
    (net (code "132") (name "unconnected-(U2-UART_RTS-PadP$4)") (class "Default")
      (node (ref "U2") (pin "P$4") (pinfunction "UART_RTS_P$4") (pintype "bidirectional"))
    )
    (net (code "133") (name "unconnected-(U2-USB_D+-PadP$20)") (class "Default")
      (node (ref "U2") (pin "P$20") (pinfunction "USB_D+_P$20") (pintype "bidirectional"))
    )
    (net (code "134") (name "unconnected-(U2-USB_D--PadP$15)") (class "Default")
      (node (ref "U2") (pin "P$15") (pinfunction "USB_D-_P$15") (pintype "bidirectional"))
    )
    (net (code "135") (name "unconnected-(U5-CLKOUT-Pad22)") (class "Default")
      (node (ref "U5") (pin "22") (pinfunction "CLKOUT_22") (pintype "bidirectional"))
    )
  )
)
